# RF_drv_v2.net
KiCad netlist of a schematic drawn in Altium Designer
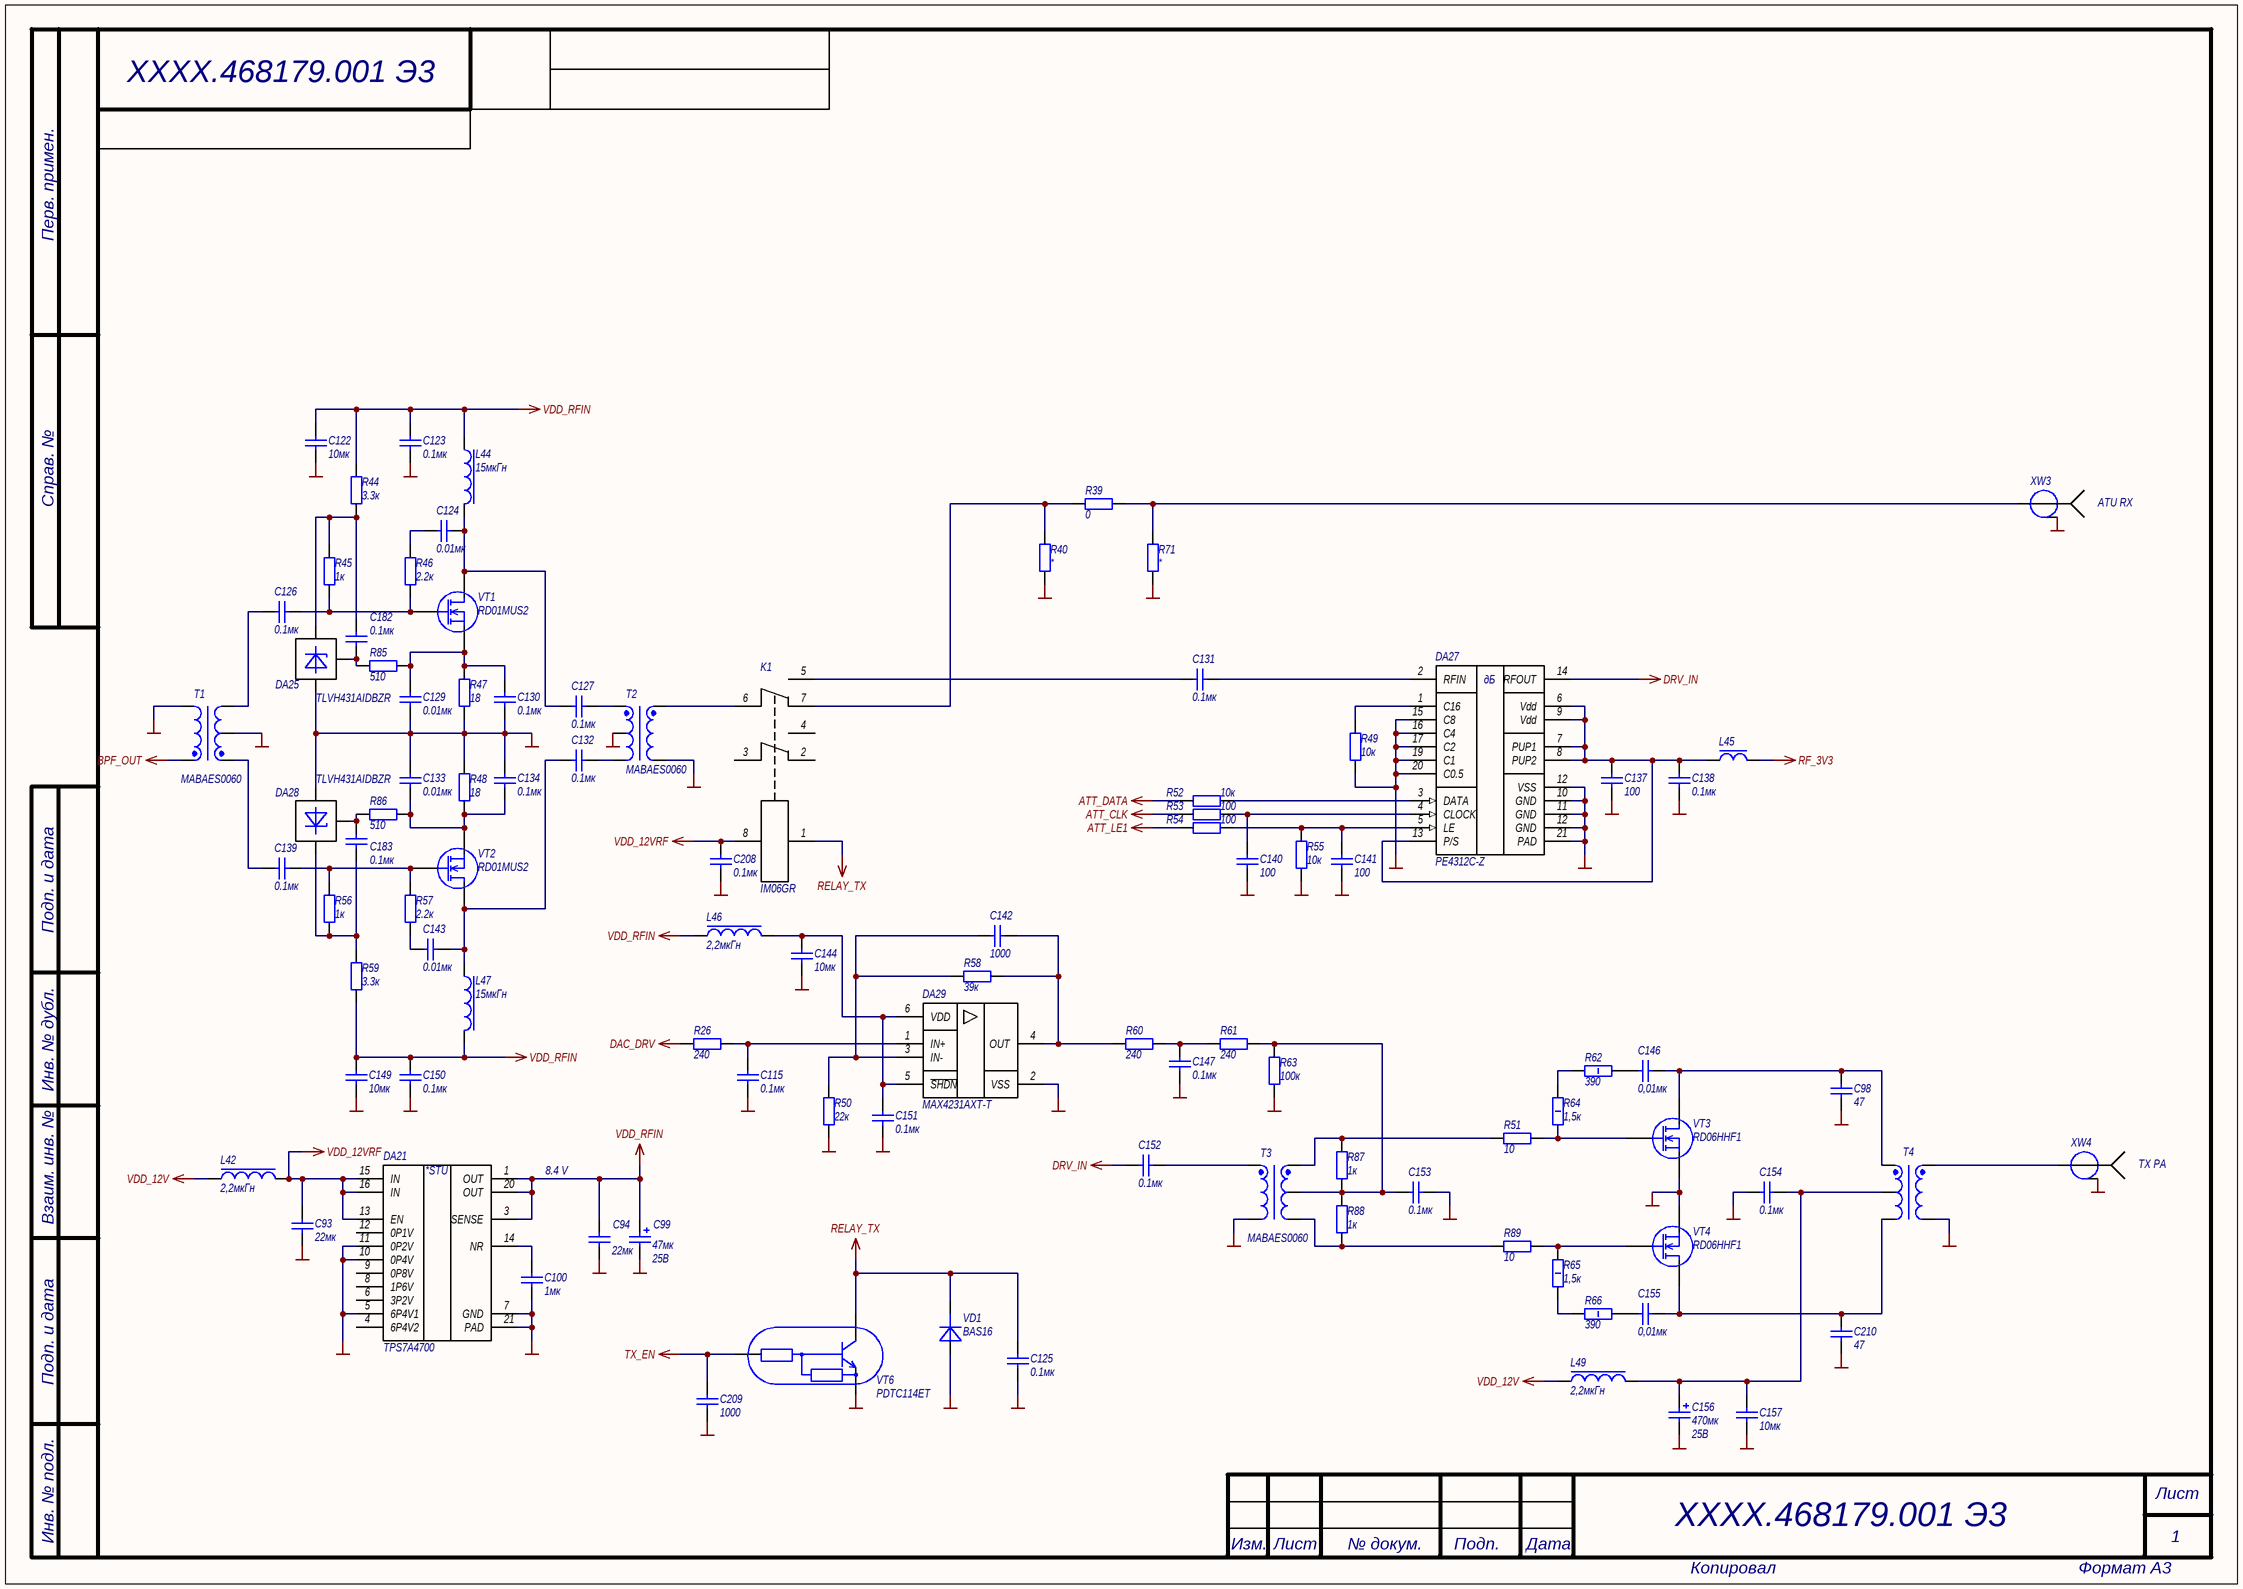
[diagram p0: RF_drv_v2.SchDoc]

(export (version "E")
  (design (tool "Eeschema 10.0.6"))
  (components
    (comp (ref "C93")
      (value "22мк")
      (footprint "CAPC2012X12L")
      (description "Кер. ЧИП-конденсатор")
      (fields (field (name "MANUFACTURER") "TDK") (field (name "TOLERANCE") "±10%"))
      (libsource (lib "nels_caps") (part "Кер.ЧИП конд. 0805 22мкФ X5R 10% 16В"))
    )
    (comp (ref "C94")
      (value "22мк")
      (footprint "CAPC2012X12L")
      (description "Кер. ЧИП-конденсатор")
      (fields (field (name "MANUFACTURER") "TDK") (field (name "TOLERANCE") "±10%"))
      (libsource (lib "nels_caps") (part "Кер.ЧИП конд. 0805 22мкФ X5R 10% 16В"))
    )
    (comp (ref "C98")
      (value "47")
      (footprint "CAPC3216X19L")
      (description "Кер. ЧИП-конденсатор")
      (fields (field (name "MANUFACTURER") "WALSIN") (field (name "TOLERANCE") "±5%"))
      (libsource (lib "nels_caps") (part "Кер.ЧИП конд. 1206 47пФ NP0 5% 2000В"))
    )
    (comp (ref "C99")
      (value "47мк")
      (footprint "CAPMP7343X28L")
      (description "Тант. ЧИП-конденсатор")
      (fields
        (field (name "TOLERANCE") "±10%")
        (field (name "POWER/VOLTAGE") "25В")
        (field (name "PUBLISHER") "Altium Limited")
      )
      (libsource (lib "nels_caps") (part "Конденсатор танталовый SMD D case 47мкФ ±10% 25B"))
    )
    (comp (ref "C100")
      (value "1мк")
      (footprint "CAPC1005X06N")
      (description "Кер. ЧИП-конденсатор")
      (fields (field (name "TOLERANCE") "±10%"))
      (libsource (lib "nels_caps") (part "Кер.ЧИП конд. 0402 1мкФ X5R 10%, 10В"))
    )
    (comp (ref "C115")
      (value "0.1мк")
      (footprint "CAPC1005X06N")
      (description "Кер. ЧИП-конденсатор")
      (fields (field (name "TOLERANCE") "±10%"))
      (libsource (lib "nels") (part "Кер.ЧИП конд. 0402 0.1мкФ X7R 10%, 16В"))
    )
    (comp (ref "C122")
      (value "10мк")
      (footprint "CAPC3225X27L")
      (description "Кер. ЧИП-конденсатор")
      (fields (field (name "MANUFACTURER") "Murata") (field (name "TOLERANCE") "±20%"))
      (libsource (lib "nels_caps") (part "Кер.ЧИП конд. 1210 10мкФ X5R 20% 50В"))
    )
    (comp (ref "C123")
      (value "0.1мк")
      (footprint "CAPC1005X06N")
      (description "Кер. ЧИП-конденсатор")
      (fields (field (name "TOLERANCE") "±10%"))
      (libsource (lib "nels") (part "Кер.ЧИП конд. 0402 0.1мкФ X7R 10%, 16В"))
    )
    (comp (ref "C124")
      (value "0.01мк")
      (footprint "CAPC1005X06N")
      (description "Кер. ЧИП-конденсатор")
      (fields (field (name "TOLERANCE") "±20%"))
      (libsource (lib "nels_caps") (part "Кер.ЧИП конд. 0402 0.01мкФ X7R 10%, 50В"))
    )
    (comp (ref "C125")
      (value "0.1мк")
      (footprint "CAPC1005X06N")
      (description "Кер. ЧИП-конденсатор")
      (fields (field (name "TOLERANCE") "±10%"))
      (libsource (lib "nels") (part "Кер.ЧИП конд. 0402 0.1мкФ X7R 10%, 16В"))
    )
    (comp (ref "C126")
      (value "0.1мк")
      (footprint "CAPC1005X06N")
      (description "Кер. ЧИП-конденсатор")
      (fields (field (name "TOLERANCE") "±10%"))
      (libsource (lib "nels") (part "Кер.ЧИП конд. 0402 0.1мкФ X7R 10%, 16В"))
    )
    (comp (ref "C127")
      (value "0.1мк")
      (footprint "CAPC1608X08L")
      (description "Кер. ЧИП-конденсатор")
      (fields (field (name "TOLERANCE") "±10%") (field (name "MANUFACTURER") "Murata"))
      (libsource (lib "nels_caps") (part "Кер.ЧИП конд. 0603 0.1мкФ X7R 10% 50В"))
    )
    (comp (ref "C129")
      (value "0.01мк")
      (footprint "CAPC1005X06N")
      (description "Кер. ЧИП-конденсатор")
      (fields (field (name "TOLERANCE") "±20%"))
      (libsource (lib "nels_caps") (part "Кер.ЧИП конд. 0402 0.01мкФ X7R 10%, 50В"))
    )
    (comp (ref "C130")
      (value "0.1мк")
      (footprint "CAPC1005X06N")
      (description "Кер. ЧИП-конденсатор")
      (fields (field (name "TOLERANCE") "±10%"))
      (libsource (lib "nels") (part "Кер.ЧИП конд. 0402 0.1мкФ X7R 10%, 16В"))
    )
    (comp (ref "C131")
      (value "0.1мк")
      (footprint "CAPC1608X08L")
      (description "Кер. ЧИП-конденсатор")
      (fields (field (name "TOLERANCE") "±10%") (field (name "MANUFACTURER") "Murata"))
      (libsource (lib "nels_caps") (part "Кер.ЧИП конд. 0603 0.1мкФ X7R 10% 50В"))
    )
    (comp (ref "C132")
      (value "0.1мк")
      (footprint "CAPC1608X08L")
      (description "Кер. ЧИП-конденсатор")
      (fields (field (name "TOLERANCE") "±10%") (field (name "MANUFACTURER") "Murata"))
      (libsource (lib "nels_caps") (part "Кер.ЧИП конд. 0603 0.1мкФ X7R 10% 50В"))
    )
    (comp (ref "C133")
      (value "0.01мк")
      (footprint "CAPC1005X06N")
      (description "Кер. ЧИП-конденсатор")
      (fields (field (name "TOLERANCE") "±20%"))
      (libsource (lib "nels_caps") (part "Кер.ЧИП конд. 0402 0.01мкФ X7R 10%, 50В"))
    )
    (comp (ref "C134")
      (value "0.1мк")
      (footprint "CAPC1005X06N")
      (description "Кер. ЧИП-конденсатор")
      (fields (field (name "TOLERANCE") "±10%"))
      (libsource (lib "nels") (part "Кер.ЧИП конд. 0402 0.1мкФ X7R 10%, 16В"))
    )
    (comp (ref "C137")
      (value "100")
      (footprint "CAPC1005X06N")
      (description "Кер. ЧИП-конденсатор")
      (fields (field (name "TOLERANCE") "±5%"))
      (libsource (lib "nels_caps") (part "Кер.ЧИП конд. 0402 100пФ NPO 5%, 50В"))
    )
    (comp (ref "C138")
      (value "0.1мк")
      (footprint "CAPC1005X06N")
      (description "Кер. ЧИП-конденсатор")
      (fields (field (name "TOLERANCE") "±10%"))
      (libsource (lib "nels") (part "Кер.ЧИП конд. 0402 0.1мкФ X7R 10%, 16В"))
    )
    (comp (ref "C139")
      (value "0.1мк")
      (footprint "CAPC1005X06N")
      (description "Кер. ЧИП-конденсатор")
      (fields (field (name "TOLERANCE") "±10%"))
      (libsource (lib "nels") (part "Кер.ЧИП конд. 0402 0.1мкФ X7R 10%, 16В"))
    )
    (comp (ref "C140")
      (value "100")
      (footprint "CAPC1005X06N")
      (description "Кер. ЧИП-конденсатор")
      (fields (field (name "TOLERANCE") "±5%"))
      (libsource (lib "nels_caps") (part "Кер.ЧИП конд. 0402 100пФ NPO 5%, 50В"))
    )
    (comp (ref "C141")
      (value "100")
      (footprint "CAPC1005X06N")
      (description "Кер. ЧИП-конденсатор")
      (fields (field (name "TOLERANCE") "±5%"))
      (libsource (lib "nels_caps") (part "Кер.ЧИП конд. 0402 100пФ NPO 5%, 50В"))
    )
    (comp (ref "C142")
      (value "1000")
      (footprint "CAPC1005X06N")
      (description "Кер. ЧИП-конденсатор")
      (fields (field (name "TOLERANCE") "±5%"))
      (libsource (lib "nels_caps") (part "Кер.ЧИП конд. 0402 1000пФ NP0 5%, 50В"))
    )
    (comp (ref "C143")
      (value "0.01мк")
      (footprint "CAPC1005X06N")
      (description "Кер. ЧИП-конденсатор")
      (fields (field (name "TOLERANCE") "±20%"))
      (libsource (lib "nels_caps") (part "Кер.ЧИП конд. 0402 0.01мкФ X7R 10%, 50В"))
    )
    (comp (ref "C144")
      (value "10мк")
      (footprint "CAPC3225X27L")
      (description "Кер. ЧИП-конденсатор")
      (fields (field (name "MANUFACTURER") "Murata") (field (name "TOLERANCE") "±20%"))
      (libsource (lib "nels_caps") (part "Кер.ЧИП конд. 1210 10мкФ X5R 20% 50В"))
    )
    (comp (ref "C146")
      (value "0,01мк")
      (footprint "CAPC2012X12L")
      (description "Кер. ЧИП-конденсатор")
      (fields (field (name "MANUFACTURER") "Murate") (field (name "TOLERANCE") "±10%"))
      (libsource (lib "nels_caps") (part "Кер.ЧИП конд. 0805 0,01 мкФ X7R 10% 250В"))
    )
    (comp (ref "C147")
      (value "0.1мк")
      (footprint "CAPC1005X06N")
      (description "Кер. ЧИП-конденсатор")
      (fields (field (name "TOLERANCE") "±10%"))
      (libsource (lib "nels") (part "Кер.ЧИП конд. 0402 0.1мкФ X7R 10%, 16В"))
    )
    (comp (ref "C149")
      (value "10мк")
      (footprint "CAPC3225X27L")
      (description "Кер. ЧИП-конденсатор")
      (fields (field (name "MANUFACTURER") "Murata") (field (name "TOLERANCE") "±20%"))
      (libsource (lib "nels_caps") (part "Кер.ЧИП конд. 1210 10мкФ X5R 20% 50В"))
    )
    (comp (ref "C150")
      (value "0.1мк")
      (footprint "CAPC1005X06N")
      (description "Кер. ЧИП-конденсатор")
      (fields (field (name "TOLERANCE") "±10%"))
      (libsource (lib "nels") (part "Кер.ЧИП конд. 0402 0.1мкФ X7R 10%, 16В"))
    )
    (comp (ref "C151")
      (value "0.1мк")
      (footprint "CAPC1005X06N")
      (description "Кер. ЧИП-конденсатор")
      (fields (field (name "TOLERANCE") "±10%"))
      (libsource (lib "nels") (part "Кер.ЧИП конд. 0402 0.1мкФ X7R 10%, 16В"))
    )
    (comp (ref "C152")
      (value "0.1мк")
      (footprint "CAPC1608X08L")
      (description "Кер. ЧИП-конденсатор")
      (fields (field (name "TOLERANCE") "±10%") (field (name "MANUFACTURER") "Murata"))
      (libsource (lib "nels_caps") (part "Кер.ЧИП конд. 0603 0.1мкФ X7R 10% 50В"))
    )
    (comp (ref "C153")
      (value "0.1мк")
      (footprint "CAPC1608X08L")
      (description "Кер. ЧИП-конденсатор")
      (fields (field (name "TOLERANCE") "±10%") (field (name "MANUFACTURER") "Murata"))
      (libsource (lib "nels_caps") (part "Кер.ЧИП конд. 0603 0.1мкФ X7R 10% 50В"))
    )
    (comp (ref "C154")
      (value "0.1мк")
      (footprint "CAPC1608X08L")
      (description "Кер. ЧИП-конденсатор")
      (fields (field (name "TOLERANCE") "±10%") (field (name "MANUFACTURER") "Murata"))
      (libsource (lib "nels_caps") (part "Кер.ЧИП конд. 0603 0.1мкФ X7R 10% 50В"))
    )
    (comp (ref "C155")
      (value "0,01мк")
      (footprint "CAPC2012X12L")
      (description "Кер. ЧИП-конденсатор")
      (fields (field (name "MANUFACTURER") "Murate") (field (name "TOLERANCE") "±10%"))
      (libsource (lib "nels_caps") (part "Кер.ЧИП конд. 0805 0,01 мкФ X7R 10% 250В"))
    )
    (comp (ref "C156")
      (value "470мк")
      (footprint "CAPAE116103X105N")
      (description "Гибридный ЧИП-конденсатор")
      (fields
        (field (name "TOLERANCE") "±20%")
        (field (name "MANUFACTURERPARTNUMBER") "EEHZK1E471P")
        (field (name "POWER/VOLTAGE") "25В")
        (field (name "PUBLISHER") "Altium Limited")
      )
      (libsource (lib "nels_caps") (part "Конденсатор гибридный SMD 470мкФ ±20% 25В"))
    )
    (comp (ref "C157")
      (value "10мк")
      (footprint "CAPC3225X27L")
      (description "Кер. ЧИП-конденсатор")
      (fields (field (name "MANUFACTURER") "Murata") (field (name "TOLERANCE") "±20%"))
      (libsource (lib "nels_caps") (part "Кер.ЧИП конд. 1210 10мкФ X5R 20% 50В"))
    )
    (comp (ref "C182")
      (value "0.1мк")
      (footprint "CAPC1005X06N")
      (description "Кер. ЧИП-конденсатор")
      (fields (field (name "TOLERANCE") "±10%"))
      (libsource (lib "nels") (part "Кер.ЧИП конд. 0402 0.1мкФ X7R 10%, 16В"))
    )
    (comp (ref "C183")
      (value "0.1мк")
      (footprint "CAPC1005X06N")
      (description "Кер. ЧИП-конденсатор")
      (fields (field (name "TOLERANCE") "±10%"))
      (libsource (lib "nels") (part "Кер.ЧИП конд. 0402 0.1мкФ X7R 10%, 16В"))
    )
    (comp (ref "C208")
      (value "0.1мк")
      (footprint "CAPC1005X06N")
      (description "Кер. ЧИП-конденсатор")
      (fields (field (name "TOLERANCE") "±10%"))
      (libsource (lib "nels") (part "Кер.ЧИП конд. 0402 0.1мкФ X7R 10%, 16В"))
    )
    (comp (ref "C209")
      (value "1000")
      (footprint "CAPC1005X06N")
      (description "Кер. ЧИП-конденсатор")
      (fields (field (name "TOLERANCE") "±5%"))
      (libsource (lib "nels_caps") (part "Кер.ЧИП конд. 0402 1000пФ NP0 5%, 50В"))
    )
    (comp (ref "C210")
      (value "47")
      (footprint "CAPC3216X19L")
      (description "Кер. ЧИП-конденсатор")
      (fields (field (name "MANUFACTURER") "WALSIN") (field (name "TOLERANCE") "±5%"))
      (libsource (lib "nels_caps") (part "Кер.ЧИП конд. 1206 47пФ NP0 5% 2000В"))
    )
    (comp (ref "DA21")
      (value "TPS7A4700")
      (footprint "QFN65P500X500X100_HS-21L")
      (description "36-V, 1-A, 4-µVRMS, RF LDO Voltage Regulator")
      (fields (field (name "MANUFACTURER") "TI"))
      (libsource (lib "nels_chip") (part "Микросхема TPS7A4700RGW"))
    )
    (comp (ref "DA25")
      (value "TLVH431AIDBZR")
      (footprint "SOT23_N")
      (description "Low-Voltage Adjustable Precision Shunt Regulator")
      (fields (field (name "MANUFACTURER") "TI"))
      (libsource (lib "nels_other") (part "ЧИП регулятор TLVH431AIDBZR"))
    )
    (comp (ref "DA27")
      (value "PE4312C-Z")
      (footprint "QFN50P400X400X80_HS-21L")
      (description "RF Digital Step Attenuator 6-bit, 31.5 dB, 1 MHz–4 GHz")
      (fields (field (name "MANUFACTURER") "Peregrine"))
      (libsource (lib "nels_chip") (part "Микросхема PE4312C-Z"))
    )
    (comp (ref "DA28")
      (value "TLVH431AIDBZR")
      (footprint "SOT23_N")
      (description "Low-Voltage Adjustable Precision Shunt Regulator")
      (fields (field (name "MANUFACTURER") "TI"))
      (libsource (lib "") (part "ЧИП регулятор TLVH431AIDBZR_1"))
    )
    (comp (ref "DA29")
      (value "MAX4231AXT-T")
      (footprint "TSOP65P210X100-6L")
      (description "High-Output-Drive, 10MHz, 10V/μs,  Rail-to-Rail I/O Op Amps with Shutdown in SC70")
      (fields (field (name "MANUFACTURER") "MAXIM"))
      (libsource (lib "nels_chip") (part "Микросхема MAX4231AXT-T"))
    )
    (comp (ref "K1")
      (value "IM06GR")
      (footprint "IM Relay GR")
      (description "Signal Relay 12VDC")
      (libsource (lib "nels_other") (part "Реле IM06GR"))
    )
    (comp (ref "L42")
      (value "2,2мкГн")
      (footprint "CSAB0420")
      (description "Molding Power Choke")
      (fields
        (field (name "MANUFACTURER") "Vishay")
        (field (name "MANUFACTURERPARTNUMBER") "IHLP1616ABER1R0M11")
      )
      (libsource (lib "nels_ind") (part "ЧИП индуктивность CSAB0420-2R2M"))
    )
    (comp (ref "L44")
      (value "15мкГн")
      (footprint "Coilcraft-1812FS")
      (description "High SRF, High Current Inductors")
      (fields
        (field (name "MANUFACTURER") "Сoilcraft")
        (field (name "MANUFACTURERPARTNUMBER") "1812PS-683KLC")
      )
      (libsource (lib "nels_ind") (part "ЧИП индуктивность 1812FS-153"))
    )
    (comp (ref "L45")
      (value "BLM18PG121SN1D")
      (footprint "INDC1608X08L")
      (description "SMD EMI Suppression Filter EMIFIL")
      (fields (field (name "MANUFACTURER") "Murata"))
      (libsource (lib "nels_ind") (part "ЧИП дроссель 0603 BLM18PG121SN1D"))
    )
    (comp (ref "L46")
      (value "2,2мкГн")
      (footprint "CSAB0420")
      (description "Molding Power Choke")
      (fields
        (field (name "MANUFACTURER") "Vishay")
        (field (name "MANUFACTURERPARTNUMBER") "IHLP1616ABER1R0M11")
      )
      (libsource (lib "nels_ind") (part "ЧИП индуктивность CSAB0420-2R2M"))
    )
    (comp (ref "L47")
      (value "15мкГн")
      (footprint "Coilcraft-1812FS")
      (description "High SRF, High Current Inductors")
      (fields
        (field (name "MANUFACTURER") "Сoilcraft")
        (field (name "MANUFACTURERPARTNUMBER") "1812PS-683KLC")
      )
      (libsource (lib "nels_ind") (part "ЧИП индуктивность 1812FS-153"))
    )
    (comp (ref "L49")
      (value "2,2мкГн")
      (footprint "CSAB0420")
      (description "Molding Power Choke")
      (fields
        (field (name "MANUFACTURER") "Vishay")
        (field (name "MANUFACTURERPARTNUMBER") "IHLP1616ABER1R0M11")
      )
      (libsource (lib "nels_ind") (part "ЧИП индуктивность CSAB0420-2R2M"))
    )
    (comp (ref "R26")
      (value "240")
      (footprint "RESC1005X06N")
      (description "ЧИП-резистор")
      (fields (field (name "TOLERANCE") "±5%"))
      (libsource (lib "nels_res") (part "Чип резистор 0402 240 Ом, 5%"))
    )
    (comp (ref "R39")
      (value "0")
      (footprint "RESC1005X06N")
      (description "ЧИП-резистор")
      (fields (field (name "TOLERANCE") "±5%"))
      (libsource (lib "nels_res") (part "Чип резистор 0402 0 Ом"))
    )
    (comp (ref "R40")
      (value "*")
      (footprint "RESC1005X06N")
      (description "ЧИП-резистор")
      (fields (field (name "TOLERANCE") "±5%") (field (name "ALTIUM_VALUE") "*"))
      (libsource (lib "nels_res") (part "Чип резистор 0402 *"))
    )
    (comp (ref "R44")
      (value "3.3к")
      (footprint "RESC1005X06N")
      (description "ЧИП-резистор")
      (fields (field (name "TOLERANCE") "±5%"))
      (libsource (lib "nels_res") (part "Чип резистор 0402 3,3 кОм, 5%"))
    )
    (comp (ref "R45")
      (value "1к")
      (footprint "RESC1005X06N")
      (description "ЧИП-резистор")
      (fields (field (name "TOLERANCE") "±5%"))
      (libsource (lib "nels_res") (part "Чип резистор 0402 1 кОм, 5%"))
    )
    (comp (ref "R46")
      (value "2.2к")
      (footprint "RESC1005X06N")
      (description "ЧИП-резистор")
      (fields (field (name "TOLERANCE") "±5%"))
      (libsource (lib "nels_res") (part "Чип резистор 0402 2,2 кОм, 5%"))
    )
    (comp (ref "R47")
      (value "18")
      (footprint "RESC2012X05L")
      (description "ЧИП-резистор")
      (fields (field (name "TOLERANCE") "±5%"))
      (libsource (lib "nels_res") (part "Чип резистор 0805 18 Ом, 5%"))
    )
    (comp (ref "R48")
      (value "18")
      (footprint "RESC2012X05L")
      (description "ЧИП-резистор")
      (fields (field (name "TOLERANCE") "±5%"))
      (libsource (lib "nels_res") (part "Чип резистор 0805 18 Ом, 5%"))
    )
    (comp (ref "R49")
      (value "10к")
      (footprint "RESC1005X06N")
      (description "ЧИП-резистор")
      (fields (field (name "TOLERANCE") "±5%"))
      (libsource (lib "") (part "Чип резистор 0402 10 кОм, 5%_2"))
    )
    (comp (ref "R50")
      (value "22к")
      (footprint "RESC1005X06N")
      (description "ЧИП-резистор")
      (fields (field (name "TOLERANCE") "±5%"))
      (libsource (lib "nels_res") (part "Чип резистор 0402 22 кОм, 5%"))
    )
    (comp (ref "R51")
      (value "10")
      (footprint "RESC1005X06N")
      (description "ЧИП-резистор")
      (fields (field (name "TOLERANCE") "±5%"))
      (libsource (lib "nels_res") (part "Чип резистор 0402 10 Ом, 5%"))
    )
    (comp (ref "R52")
      (value "10к")
      (footprint "RESC1005X06N")
      (description "ЧИП-резистор")
      (fields (field (name "TOLERANCE") "±5%"))
      (libsource (lib "nels_res") (part "Чип резистор 0402 10 кОм, 5%"))
    )
    (comp (ref "R53")
      (value "100")
      (footprint "RESC1005X06N")
      (description "ЧИП-резистор")
      (fields (field (name "TOLERANCE") "±5%"))
      (libsource (lib "nels_res") (part "Чип резистор 0402 100 Ом, 5%"))
    )
    (comp (ref "R54")
      (value "100")
      (footprint "RESC1005X06N")
      (description "ЧИП-резистор")
      (fields (field (name "TOLERANCE") "±5%"))
      (libsource (lib "nels_res") (part "Чип резистор 0402 100 Ом, 5%"))
    )
    (comp (ref "R55")
      (value "10к")
      (footprint "RESC1005X06N")
      (description "ЧИП-резистор")
      (fields (field (name "TOLERANCE") "±5%"))
      (libsource (lib "") (part "Чип резистор 0402 10 кОм, 5%_1"))
    )
    (comp (ref "R56")
      (value "1к")
      (footprint "RESC1005X06N")
      (description "ЧИП-резистор")
      (fields (field (name "TOLERANCE") "±5%"))
      (libsource (lib "nels_res") (part "Чип резистор 0402 1 кОм, 5%"))
    )
    (comp (ref "R57")
      (value "2.2к")
      (footprint "RESC1005X06N")
      (description "ЧИП-резистор")
      (fields (field (name "TOLERANCE") "±5%"))
      (libsource (lib "nels_res") (part "Чип резистор 0402 2,2 кОм, 5%"))
    )
    (comp (ref "R58")
      (value "39к")
      (footprint "RESC1005X06N")
      (description "ЧИП-резистор")
      (fields (field (name "TOLERANCE") "±5%"))
      (libsource (lib "nels_res") (part "Чип резистор 0402 39 кОм, 5%"))
    )
    (comp (ref "R59")
      (value "3.3к")
      (footprint "RESC1005X06N")
      (description "ЧИП-резистор")
      (fields (field (name "TOLERANCE") "±5%"))
      (libsource (lib "nels_res") (part "Чип резистор 0402 3,3 кОм, 5%"))
    )
    (comp (ref "R60")
      (value "240")
      (footprint "RESC1005X06N")
      (description "ЧИП-резистор")
      (fields (field (name "TOLERANCE") "±5%"))
      (libsource (lib "nels_res") (part "Чип резистор 0402 240 Ом, 5%"))
    )
    (comp (ref "R61")
      (value "240")
      (footprint "RESC1005X06N")
      (description "ЧИП-резистор")
      (fields (field (name "TOLERANCE") "±5%"))
      (libsource (lib "nels_res") (part "Чип резистор 0402 240 Ом, 5%"))
    )
    (comp (ref "R62")
      (value "390")
      (footprint "RESC3216X04L")
      (description "ЧИП-резистор")
      (fields (field (name "TOLERANCE") "±5%") (field (name "MANUFACTURER") "ROHM"))
      (libsource (lib "nels_res") (part "Чип резистор 1206 390 Ом, 5%"))
    )
    (comp (ref "R63")
      (value "100к")
      (footprint "RESC1005X06N")
      (description "ЧИП-резистор")
      (fields (field (name "TOLERANCE") "±5%"))
      (libsource (lib "nels_res") (part "Чип резистор 0402 100 кОм, 5%"))
    )
    (comp (ref "R64")
      (value "1,5к")
      (footprint "RESC3216X04L")
      (description "ЧИП-резистор")
      (fields (field (name "TOLERANCE") "±5%") (field (name "MANUFACTURER") "ROHM"))
      (libsource (lib "nels_res") (part "Чип резистор 1206 1,5 кОм, 5%"))
    )
    (comp (ref "R65")
      (value "1,5к")
      (footprint "RESC3216X04L")
      (description "ЧИП-резистор")
      (fields (field (name "TOLERANCE") "±5%") (field (name "MANUFACTURER") "ROHM"))
      (libsource (lib "nels_res") (part "Чип резистор 1206 1,5 кОм, 5%"))
    )
    (comp (ref "R66")
      (value "390")
      (footprint "RESC3216X04L")
      (description "ЧИП-резистор")
      (fields (field (name "TOLERANCE") "±5%") (field (name "MANUFACTURER") "ROHM"))
      (libsource (lib "nels_res") (part "Чип резистор 1206 390 Ом, 5%"))
    )
    (comp (ref "R71")
      (value "*")
      (footprint "RESC1005X06N")
      (description "ЧИП-резистор")
      (fields (field (name "TOLERANCE") "±5%") (field (name "ALTIUM_VALUE") "*"))
      (libsource (lib "nels_res") (part "Чип резистор 0402 *"))
    )
    (comp (ref "R85")
      (value "510")
      (footprint "RESC1005X06N")
      (description "ЧИП-резистор")
      (fields (field (name "TOLERANCE") "±5%"))
      (libsource (lib "nels_res") (part "Чип резистор 0402 510 Ом, 5%"))
    )
    (comp (ref "R86")
      (value "510")
      (footprint "RESC1005X06N")
      (description "ЧИП-резистор")
      (fields (field (name "TOLERANCE") "±5%"))
      (libsource (lib "nels_res") (part "Чип резистор 0402 510 Ом, 5%"))
    )
    (comp (ref "R87")
      (value "1к")
      (footprint "RESC1005X06N")
      (description "ЧИП-резистор")
      (fields (field (name "TOLERANCE") "±5%"))
      (libsource (lib "nels_res") (part "Чип резистор 0402 1 кОм, 5%"))
    )
    (comp (ref "R88")
      (value "1к")
      (footprint "RESC1005X06N")
      (description "ЧИП-резистор")
      (fields (field (name "TOLERANCE") "±5%"))
      (libsource (lib "nels_res") (part "Чип резистор 0402 1 кОм, 5%"))
    )
    (comp (ref "R89")
      (value "10")
      (footprint "RESC1005X06N")
      (description "ЧИП-резистор")
      (fields (field (name "TOLERANCE") "±5%"))
      (libsource (lib "nels_res") (part "Чип резистор 0402 10 Ом, 5%"))
    )
    (comp (ref "T1")
      (value "MABAES0060")
      (footprint "SM-22 package")
      (description "RF 1:1 Flux Coupled Transformer 0.3 - 200 MHz")
      (fields (field (name "MANUFACTURER") "MACOM"))
      (libsource (lib "nels_ind") (part "ЧИП трансформатор MABAES0060"))
    )
    (comp (ref "T2")
      (value "MABAES0060")
      (footprint "SM-22 package")
      (description "RF 1:1 Flux Coupled Transformer 0.3 - 200 MHz")
      (fields (field (name "MANUFACTURER") "MACOM"))
      (libsource (lib "nels_ind") (part "ЧИП трансформатор MABAES0060"))
    )
    (comp (ref "T3")
      (value "MABAES0060")
      (footprint "SM-22 package")
      (description "RF 1:1 Flux Coupled Transformer 0.3 - 200 MHz")
      (fields (field (name "MANUFACTURER") "MACOM"))
      (libsource (lib "") (part "ЧИП трансформатор MABAES0060_1"))
    )
    (comp (ref "T4")
      (value "Трансформатор PUM_OUT")
      (footprint "Transformer_KV_PA20_0UT_2xBN-43-302_V1")
      (fields
        (field (name "MANUFACTURER") "НЕЛС")
        (field (name "MANUFACTURER PART NUMBER") "Трансформатор PUM_OUT АНЕЛ.671143.003")
      )
      (libsource (lib "nels_ind") (part "Transformer_KV_PA20_OUT"))
    )
    (comp (ref "VD1")
      (value "BAS16")
      (footprint "SOT23_N")
      (description "High-speed switching diodes")
      (fields (field (name "MANUFACTURER") "Nexperia"))
      (libsource (lib "nels_other") (part "ЧИП диод BAS16"))
    )
    (comp (ref "VT1")
      (value "RD01MUS2")
      (footprint "SOT89-150P330X160-3N")
      (description "Silicon MOSFET Power Transistor 520MHz, 1W, 7.2V")
      (libsource (lib "nels_other") (part "ЧИП транзистор RD01MUS2"))
    )
    (comp (ref "VT2")
      (value "RD01MUS2")
      (footprint "SOT89-150P330X160-3N")
      (description "Silicon MOSFET Power Transistor 520MHz, 1W, 7.2V")
      (libsource (lib "nels_other") (part "ЧИП транзистор RD01MUS2"))
    )
    (comp (ref "VT3")
      (value "RD06HHF1")
      (footprint "TO-220HS")
      (description "Silicon MOSFET Power Transistor 30MHz,6W")
      (libsource (lib "nels_other") (part "ЧИП транзистор RD06HHF1"))
    )
    (comp (ref "VT4")
      (value "RD06HHF1")
      (footprint "TO-220HS")
      (description "Silicon MOSFET Power Transistor 30MHz,6W")
      (libsource (lib "nels_other") (part "ЧИП транзистор RD06HHF1"))
    )
    (comp (ref "VT6")
      (value "PDTC114ET")
      (footprint "SOT23_N")
      (description "NPN resistor-equipped transistors;  R1 = 10 k, R2 = 10")
      (libsource (lib "nels_other") (part "ЧИП транзистор PDTC114ET"))
    )
    (comp (ref "XW3")
      (value "SMA-JR")
      (footprint "SMA-JR")
      (description "SMA-JR Разъем SMA гнездо на плату, прямой угол")
      (libsource (lib "nels_conn") (part "Соединитель коаксиальный SMA-JR"))
    )
    (comp (ref "XW4")
      (value "SMA-JR")
      (footprint "SMA-JR")
      (description "SMA-JR Разъем SMA гнездо на плату, прямой угол")
      (libsource (lib "nels_conn") (part "Соединитель коаксиальный SMA-JR"))
    )
  )
  (nets
    (net (code "1") (name "ATT_CLK") (class "Default")
      (node (ref "R53") (pin "2") (pinfunction "2_2") (pintype "passive"))
    )
    (net (code "2") (name "ATT_DATA") (class "Default")
      (node (ref "R52") (pin "2") (pinfunction "2_2") (pintype "passive"))
    )
    (net (code "3") (name "ATT_LE1") (class "Default")
      (node (ref "R54") (pin "2") (pinfunction "2_2") (pintype "passive"))
    )
    (net (code "4") (name "BPF_OUT") (class "Default")
      (node (ref "T1") (pin "5") (pinfunction "PRIMARY_DOT_5") (pintype "passive"))
    )
    (net (code "5") (name "DAC_DRV") (class "Default")
      (node (ref "R26") (pin "1") (pinfunction "1_1") (pintype "passive"))
    )
    (net (code "6") (name "DRV_IN") (class "Default")
      (node (ref "C152") (pin "2") (pinfunction "2_2") (pintype "passive"))
      (node (ref "DA27") (pin "14") (pinfunction "RFOUT_14") (pintype "passive"))
    )
    (net (code "7") (name "GND") (class "Default")
      (node (ref "C100") (pin "1") (pinfunction "1_1") (pintype "passive"))
      (node (ref "C115") (pin "2") (pinfunction "2_2") (pintype "passive"))
      (node (ref "C122") (pin "1") (pinfunction "1_1") (pintype "passive"))
      (node (ref "C123") (pin "2") (pinfunction "2_2") (pintype "passive"))
      (node (ref "C125") (pin "2") (pinfunction "2_2") (pintype "passive"))
      (node (ref "C129") (pin "2") (pinfunction "2_2") (pintype "passive"))
      (node (ref "C130") (pin "2") (pinfunction "2_2") (pintype "passive"))
      (node (ref "C133") (pin "1") (pinfunction "1_1") (pintype "passive"))
      (node (ref "C134") (pin "1") (pinfunction "1_1") (pintype "passive"))
      (node (ref "C137") (pin "1") (pinfunction "1_1") (pintype "passive"))
      (node (ref "C138") (pin "1") (pinfunction "1_1") (pintype "passive"))
      (node (ref "C140") (pin "1") (pinfunction "1_1") (pintype "passive"))
      (node (ref "C141") (pin "1") (pinfunction "1_1") (pintype "passive"))
      (node (ref "C144") (pin "1") (pinfunction "1_1") (pintype "passive"))
      (node (ref "C147") (pin "2") (pinfunction "2_2") (pintype "passive"))
      (node (ref "C149") (pin "1") (pinfunction "1_1") (pintype "passive"))
      (node (ref "C150") (pin "2") (pinfunction "2_2") (pintype "passive"))
      (node (ref "C151") (pin "2") (pinfunction "2_2") (pintype "passive"))
      (node (ref "C153") (pin "1") (pinfunction "1_1") (pintype "passive"))
      (node (ref "C154") (pin "1") (pinfunction "1_1") (pintype "passive"))
      (node (ref "C156") (pin "2") (pinfunction "2_2") (pintype "passive"))
      (node (ref "C157") (pin "1") (pinfunction "1_1") (pintype "passive"))
      (node (ref "C208") (pin "2") (pinfunction "2_2") (pintype "passive"))
      (node (ref "C209") (pin "2") (pinfunction "2_2") (pintype "passive"))
      (node (ref "C210") (pin "2") (pinfunction "2_2") (pintype "passive"))
      (node (ref "C93") (pin "1") (pinfunction "1_1") (pintype "passive"))
      (node (ref "C94") (pin "1") (pinfunction "1_1") (pintype "passive"))
      (node (ref "C98") (pin "2") (pinfunction "2_2") (pintype "passive"))
      (node (ref "C99") (pin "2") (pinfunction "2_2") (pintype "passive"))
      (node (ref "DA21") (pin "10") (pinfunction "0P4V_10") (pintype "passive"))
      (node (ref "DA21") (pin "11") (pinfunction "0P2V_11") (pintype "passive"))
      (node (ref "DA21") (pin "21") (pinfunction "PAD_21") (pintype "passive"))
      (node (ref "DA21") (pin "5") (pinfunction "6P4V1_5") (pintype "passive"))
      (node (ref "DA21") (pin "7") (pinfunction "GND_7") (pintype "passive"))
      (node (ref "DA25") (pin "3") (pinfunction "A_3") (pintype "passive"))
      (node (ref "DA27") (pin "10") (pinfunction "GND_10") (pintype "power_in"))
      (node (ref "DA27") (pin "11") (pinfunction "GND_11") (pintype "power_in"))
      (node (ref "DA27") (pin "12") (pinfunction "GND_12") (pintype "power_in"))
      (node (ref "DA27") (pin "15") (pinfunction "C8_15") (pintype "passive"))
      (node (ref "DA27") (pin "16") (pinfunction "C4_16") (pintype "passive"))
      (node (ref "DA27") (pin "17") (pinfunction "C2_17") (pintype "passive"))
      (node (ref "DA27") (pin "19") (pinfunction "C1_19") (pintype "passive"))
      (node (ref "DA27") (pin "20") (pinfunction "C0.5_20") (pintype "passive"))
      (node (ref "DA27") (pin "21") (pinfunction "PAD_21") (pintype "power_in"))
      (node (ref "DA28") (pin "3") (pinfunction "A_3") (pintype "passive"))
      (node (ref "DA29") (pin "2") (pinfunction "VSS_2") (pintype "passive"))
      (node (ref "R40") (pin "2") (pinfunction "2_2") (pintype "passive"))
      (node (ref "R47") (pin "2") (pinfunction "2_2") (pintype "passive"))
      (node (ref "R48") (pin "1") (pinfunction "1_1") (pintype "passive"))
      (node (ref "R49") (pin "1") (pinfunction "1_1") (pintype "passive"))
      (node (ref "R50") (pin "1") (pinfunction "1_1") (pintype "passive"))
      (node (ref "R55") (pin "2") (pinfunction "2_2") (pintype "passive"))
      (node (ref "R63") (pin "2") (pinfunction "2_2") (pintype "passive"))
      (node (ref "R71") (pin "2") (pinfunction "2_2") (pintype "passive"))
      (node (ref "T1") (pin "2") (pinfunction "SECONARY_CT_2") (pintype "passive"))
      (node (ref "T1") (pin "4") (pinfunction "PRIMARY_4") (pintype "passive"))
      (node (ref "T2") (pin "2") (pinfunction "SECONARY_CT_2") (pintype "passive"))
      (node (ref "T2") (pin "4") (pinfunction "PRIMARY_4") (pintype "passive"))
      (node (ref "T3") (pin "4") (pinfunction "PRIMARY_4") (pintype "passive"))
      (node (ref "T4") (pin "5") (pinfunction "SECONDARY_5") (pintype "passive"))
      (node (ref "VD1") (pin "1") (pinfunction "A_1") (pintype "passive"))
      (node (ref "VT3") (pin "2") (pinfunction "S_2") (pintype "passive"))
      (node (ref "VT4") (pin "2") (pinfunction "S_2") (pintype "passive"))
      (node (ref "VT6") (pin "2") (pinfunction "E_2") (pintype "passive"))
      (node (ref "XW3") (pin "2") (pinfunction "2_2") (pintype "passive"))
      (node (ref "XW4") (pin "2") (pinfunction "2_2") (pintype "passive"))
    )
    (net (code "8") (name "Net-(C124-Pad1)") (class "Default")
      (node (ref "C124") (pin "1") (pinfunction "1_1") (pintype "passive"))
      (node (ref "R46") (pin "1") (pinfunction "1_1") (pintype "passive"))
    )
    (net (code "9") (name "Net-(C131-Pad2)") (class "Default")
      (node (ref "C131") (pin "2") (pinfunction "2_2") (pintype "passive"))
      (node (ref "K1") (pin "5") (pintype "passive"))
    )
    (net (code "10") (name "Net-(C143-Pad1)") (class "Default")
      (node (ref "C143") (pin "1") (pinfunction "1_1") (pintype "passive"))
      (node (ref "R57") (pin "2") (pinfunction "2_2") (pintype "passive"))
    )
    (net (code "11") (name "Net-(C146-Pad2)") (class "Default")
      (node (ref "C146") (pin "2") (pinfunction "2_2") (pintype "passive"))
      (node (ref "R62") (pin "2") (pinfunction "2_2") (pintype "passive"))
    )
    (net (code "12") (name "Net-(C147-Pad1)") (class "Default")
      (node (ref "C147") (pin "1") (pinfunction "1_1") (pintype "passive"))
      (node (ref "R60") (pin "2") (pinfunction "2_2") (pintype "passive"))
      (node (ref "R61") (pin "1") (pinfunction "1_1") (pintype "passive"))
    )
    (net (code "13") (name "Net-(C155-Pad2)") (class "Default")
      (node (ref "C155") (pin "2") (pinfunction "2_2") (pintype "passive"))
      (node (ref "R66") (pin "2") (pinfunction "2_2") (pintype "passive"))
    )
    (net (code "14") (name "Net-(DA21-NR)") (class "Default")
      (node (ref "C100") (pin "2") (pinfunction "2_2") (pintype "passive"))
      (node (ref "DA21") (pin "14") (pinfunction "NR_14") (pintype "passive"))
    )
    (net (code "15") (name "Net-(DA25-K)") (class "Default")
      (node (ref "C182") (pin "1") (pinfunction "1_1") (pintype "passive"))
      (node (ref "DA25") (pin "2") (pinfunction "K_2") (pintype "passive"))
      (node (ref "R44") (pin "1") (pinfunction "1_1") (pintype "passive"))
      (node (ref "R45") (pin "1") (pinfunction "1_1") (pintype "passive"))
    )
    (net (code "16") (name "Net-(DA25-REF)") (class "Default")
      (node (ref "C182") (pin "2") (pinfunction "2_2") (pintype "passive"))
      (node (ref "DA25") (pin "1") (pinfunction "REF_1") (pintype "passive"))
      (node (ref "R85") (pin "1") (pinfunction "1_1") (pintype "passive"))
    )
    (net (code "17") (name "Net-(DA27-C16)") (class "Default")
      (node (ref "DA27") (pin "1") (pinfunction "C16_1") (pintype "passive"))
      (node (ref "R49") (pin "2") (pinfunction "2_2") (pintype "passive"))
    )
    (net (code "18") (name "Net-(DA27-CLOCK)") (class "Default")
      (node (ref "C140") (pin "2") (pinfunction "2_2") (pintype "passive"))
      (node (ref "DA27") (pin "4") (pinfunction "CLOCK_4") (pintype "input"))
      (node (ref "R53") (pin "1") (pinfunction "1_1") (pintype "passive"))
    )
    (net (code "19") (name "Net-(DA27-DATA)") (class "Default")
      (node (ref "DA27") (pin "3") (pinfunction "DATA_3") (pintype "input"))
      (node (ref "R52") (pin "1") (pinfunction "1_1") (pintype "passive"))
    )
    (net (code "20") (name "Net-(DA27-LE)") (class "Default")
      (node (ref "C141") (pin "2") (pinfunction "2_2") (pintype "passive"))
      (node (ref "DA27") (pin "5") (pinfunction "LE_5") (pintype "input"))
      (node (ref "R54") (pin "1") (pinfunction "1_1") (pintype "passive"))
      (node (ref "R55") (pin "1") (pinfunction "1_1") (pintype "passive"))
    )
    (net (code "21") (name "Net-(DA27-PUP1)") (class "Default")
      (node (ref "C137") (pin "2") (pinfunction "2_2") (pintype "passive"))
      (node (ref "C138") (pin "2") (pinfunction "2_2") (pintype "passive"))
      (node (ref "DA27") (pin "13") (pinfunction "P/S_13") (pintype "passive"))
      (node (ref "DA27") (pin "6") (pinfunction "Vdd_6") (pintype "power_in"))
      (node (ref "DA27") (pin "7") (pinfunction "PUP1_7") (pintype "passive"))
      (node (ref "DA27") (pin "8") (pinfunction "PUP2_8") (pintype "passive"))
      (node (ref "DA27") (pin "9") (pinfunction "Vdd_9") (pintype "power_in"))
      (node (ref "L45") (pin "1") (pinfunction "1_1") (pintype "passive"))
    )
    (net (code "22") (name "Net-(DA27-RFIN)") (class "Default")
      (node (ref "C131") (pin "1") (pinfunction "1_1") (pintype "passive"))
      (node (ref "DA27") (pin "2") (pinfunction "RFIN_2") (pintype "passive"))
    )
    (net (code "23") (name "Net-(DA28-K)") (class "Default")
      (node (ref "C183") (pin "2") (pinfunction "2_2") (pintype "passive"))
      (node (ref "DA28") (pin "2") (pinfunction "K_2") (pintype "passive"))
      (node (ref "R56") (pin "2") (pinfunction "2_2") (pintype "passive"))
      (node (ref "R59") (pin "2") (pinfunction "2_2") (pintype "passive"))
    )
    (net (code "24") (name "Net-(DA28-REF)") (class "Default")
      (node (ref "C183") (pin "1") (pinfunction "1_1") (pintype "passive"))
      (node (ref "DA28") (pin "1") (pinfunction "REF_1") (pintype "passive"))
      (node (ref "R86") (pin "1") (pinfunction "1_1") (pintype "passive"))
    )
    (net (code "25") (name "Net-(DA29-IN+)") (class "Default")
      (node (ref "C115") (pin "1") (pinfunction "1_1") (pintype "passive"))
      (node (ref "DA29") (pin "1") (pinfunction "IN+_1") (pintype "passive"))
      (node (ref "R26") (pin "2") (pinfunction "2_2") (pintype "passive"))
    )
    (net (code "26") (name "Net-(DA29-IN-)") (class "Default")
      (node (ref "C142") (pin "1") (pinfunction "1_1") (pintype "passive"))
      (node (ref "DA29") (pin "3") (pinfunction "IN-_3") (pintype "passive"))
      (node (ref "R50") (pin "2") (pinfunction "2_2") (pintype "passive"))
      (node (ref "R58") (pin "1") (pinfunction "1_1") (pintype "passive"))
    )
    (net (code "27") (name "Net-(DA29-OUT)") (class "Default")
      (node (ref "C142") (pin "2") (pinfunction "2_2") (pintype "passive"))
      (node (ref "DA29") (pin "4") (pinfunction "OUT_4") (pintype "passive"))
      (node (ref "R58") (pin "2") (pinfunction "2_2") (pintype "passive"))
      (node (ref "R60") (pin "1") (pinfunction "1_1") (pintype "passive"))
    )
    (net (code "28") (name "Net-(DA29-VDD)") (class "Default")
      (node (ref "C144") (pin "2") (pinfunction "2_2") (pintype "passive"))
      (node (ref "C151") (pin "1") (pinfunction "1_1") (pintype "passive"))
      (node (ref "DA29") (pin "5") (pinfunction "~{SHDN}_5") (pintype "passive"))
      (node (ref "DA29") (pin "6") (pinfunction "VDD_6") (pintype "passive"))
      (node (ref "L46") (pin "2") (pinfunction "2_2") (pintype "passive"))
    )
    (net (code "29") (name "Net-(K1-Pad7)") (class "Default")
      (node (ref "K1") (pin "7") (pintype "passive"))
      (node (ref "R39") (pin "1") (pinfunction "1_1") (pintype "passive"))
      (node (ref "R40") (pin "1") (pinfunction "1_1") (pintype "passive"))
    )
    (net (code "30") (name "Net-(R39-Pad2)") (class "Default")
      (node (ref "R39") (pin "2") (pinfunction "2_2") (pintype "passive"))
      (node (ref "R71") (pin "1") (pinfunction "1_1") (pintype "passive"))
      (node (ref "XW3") (pin "1") (pinfunction "1_1") (pintype "passive"))
    )
    (net (code "31") (name "Net-(R62-Pad1)") (class "Default")
      (node (ref "R62") (pin "1") (pinfunction "1_1") (pintype "passive"))
      (node (ref "R64") (pin "2") (pinfunction "2_2") (pintype "passive"))
    )
    (net (code "32") (name "Net-(R65-Pad1)") (class "Default")
      (node (ref "R65") (pin "1") (pinfunction "1_1") (pintype "passive"))
      (node (ref "R66") (pin "1") (pinfunction "1_1") (pintype "passive"))
    )
    (net (code "33") (name "Net-(T1-SECONDARY)") (class "Default")
      (node (ref "C126") (pin "2") (pinfunction "2_2") (pintype "passive"))
      (node (ref "T1") (pin "3") (pinfunction "SECONDARY_3") (pintype "passive"))
    )
    (net (code "34") (name "Net-(T1-SECONDARY_DOT)") (class "Default")
      (node (ref "C139") (pin "2") (pinfunction "2_2") (pintype "passive"))
      (node (ref "T1") (pin "1") (pinfunction "SECONDARY_DOT_1") (pintype "passive"))
    )
    (net (code "35") (name "Net-(T2-PRIMARY_DOT)") (class "Default")
      (node (ref "K1") (pin "6") (pintype "passive"))
      (node (ref "T2") (pin "5") (pinfunction "PRIMARY_DOT_5") (pintype "passive"))
    )
    (net (code "36") (name "Net-(T2-SECONDARY)") (class "Default")
      (node (ref "C132") (pin "1") (pinfunction "1_1") (pintype "passive"))
      (node (ref "T2") (pin "3") (pinfunction "SECONDARY_3") (pintype "passive"))
    )
    (net (code "37") (name "Net-(T2-SECONDARY_DOT)") (class "Default")
      (node (ref "C127") (pin "1") (pinfunction "1_1") (pintype "passive"))
      (node (ref "T2") (pin "1") (pinfunction "SECONDARY_DOT_1") (pintype "passive"))
    )
    (net (code "38") (name "Net-(T3-PRIMARY_DOT)") (class "Default")
      (node (ref "C152") (pin "1") (pinfunction "1_1") (pintype "passive"))
      (node (ref "T3") (pin "5") (pinfunction "PRIMARY_DOT_5") (pintype "passive"))
    )
    (net (code "39") (name "Net-(T3-SECONARY_CT)") (class "Default")
      (node (ref "C153") (pin "2") (pinfunction "2_2") (pintype "passive"))
      (node (ref "R61") (pin "2") (pinfunction "2_2") (pintype "passive"))
      (node (ref "R63") (pin "1") (pinfunction "1_1") (pintype "passive"))
      (node (ref "R87") (pin "2") (pinfunction "2_2") (pintype "passive"))
      (node (ref "R88") (pin "1") (pinfunction "1_1") (pintype "passive"))
      (node (ref "T3") (pin "2") (pinfunction "SECONARY_CT_2") (pintype "passive"))
    )
    (net (code "40") (name "Net-(T3-SECONDARY)") (class "Default")
      (node (ref "R88") (pin "2") (pinfunction "2_2") (pintype "passive"))
      (node (ref "R89") (pin "1") (pinfunction "1_1") (pintype "passive"))
      (node (ref "T3") (pin "3") (pinfunction "SECONDARY_3") (pintype "passive"))
    )
    (net (code "41") (name "Net-(T3-SECONDARY_DOT)") (class "Default")
      (node (ref "R51") (pin "1") (pinfunction "1_1") (pintype "passive"))
      (node (ref "R87") (pin "1") (pinfunction "1_1") (pintype "passive"))
      (node (ref "T3") (pin "1") (pinfunction "SECONDARY_DOT_1") (pintype "passive"))
    )
    (net (code "42") (name "Net-(T4-CT)") (class "Default")
      (node (ref "C154") (pin "2") (pinfunction "2_2") (pintype "passive"))
      (node (ref "C156") (pin "1") (pinfunction "1_1") (pintype "passive"))
      (node (ref "C157") (pin "2") (pinfunction "2_2") (pintype "passive"))
      (node (ref "L49") (pin "2") (pinfunction "2_2") (pintype "passive"))
      (node (ref "T4") (pin "2") (pinfunction "CT_2") (pintype "passive"))
    )
    (net (code "43") (name "Net-(T4-PRIMARY)") (class "Default")
      (node (ref "C155") (pin "1") (pinfunction "1_1") (pintype "passive"))
      (node (ref "C210") (pin "1") (pinfunction "1_1") (pintype "passive"))
      (node (ref "T4") (pin "1") (pinfunction "PRIMARY_1") (pintype "passive"))
      (node (ref "VT4") (pin "3") (pinfunction "D_3") (pintype "passive"))
    )
    (net (code "44") (name "Net-(T4-PRIMARY_DOT)") (class "Default")
      (node (ref "C146") (pin "1") (pinfunction "1_1") (pintype "passive"))
      (node (ref "C98") (pin "1") (pinfunction "1_1") (pintype "passive"))
      (node (ref "T4") (pin "3") (pinfunction "PRIMARY_DOT_3") (pintype "passive"))
      (node (ref "VT3") (pin "3") (pinfunction "D_3") (pintype "passive"))
    )
    (net (code "45") (name "Net-(T4-SECONDARY_DOT)") (class "Default")
      (node (ref "T4") (pin "4") (pinfunction "SECONDARY_DOT_4") (pintype "passive"))
      (node (ref "XW4") (pin "1") (pinfunction "1_1") (pintype "passive"))
    )
    (net (code "46") (name "Net-(VT1-D)") (class "Default")
      (node (ref "C124") (pin "2") (pinfunction "2_2") (pintype "passive"))
      (node (ref "C127") (pin "2") (pinfunction "2_2") (pintype "passive"))
      (node (ref "L44") (pin "2") (pinfunction "2_2") (pintype "passive"))
      (node (ref "VT1") (pin "3") (pinfunction "D_3") (pintype "passive"))
    )
    (net (code "47") (name "Net-(VT1-GATE)") (class "Default")
      (node (ref "C126") (pin "1") (pinfunction "1_1") (pintype "passive"))
      (node (ref "R45") (pin "2") (pinfunction "2_2") (pintype "passive"))
      (node (ref "R46") (pin "2") (pinfunction "2_2") (pintype "passive"))
      (node (ref "VT1") (pin "1") (pinfunction "GATE_1") (pintype "passive"))
    )
    (net (code "48") (name "Net-(VT1-S)") (class "Default")
      (node (ref "C129") (pin "1") (pinfunction "1_1") (pintype "passive"))
      (node (ref "C130") (pin "1") (pinfunction "1_1") (pintype "passive"))
      (node (ref "R47") (pin "1") (pinfunction "1_1") (pintype "passive"))
      (node (ref "R85") (pin "2") (pinfunction "2_2") (pintype "passive"))
      (node (ref "VT1") (pin "2") (pinfunction "S_2") (pintype "passive"))
    )
    (net (code "49") (name "Net-(VT2-D)") (class "Default")
      (node (ref "C132") (pin "2") (pinfunction "2_2") (pintype "passive"))
      (node (ref "C143") (pin "2") (pinfunction "2_2") (pintype "passive"))
      (node (ref "L47") (pin "1") (pinfunction "1_1") (pintype "passive"))
      (node (ref "VT2") (pin "3") (pinfunction "D_3") (pintype "passive"))
    )
    (net (code "50") (name "Net-(VT2-GATE)") (class "Default")
      (node (ref "C139") (pin "1") (pinfunction "1_1") (pintype "passive"))
      (node (ref "R56") (pin "1") (pinfunction "1_1") (pintype "passive"))
      (node (ref "R57") (pin "1") (pinfunction "1_1") (pintype "passive"))
      (node (ref "VT2") (pin "1") (pinfunction "GATE_1") (pintype "passive"))
    )
    (net (code "51") (name "Net-(VT2-S)") (class "Default")
      (node (ref "C133") (pin "2") (pinfunction "2_2") (pintype "passive"))
      (node (ref "C134") (pin "2") (pinfunction "2_2") (pintype "passive"))
      (node (ref "R48") (pin "2") (pinfunction "2_2") (pintype "passive"))
      (node (ref "R86") (pin "2") (pinfunction "2_2") (pintype "passive"))
      (node (ref "VT2") (pin "2") (pinfunction "S_2") (pintype "passive"))
    )
    (net (code "52") (name "Net-(VT3-GATE)") (class "Default")
      (node (ref "R51") (pin "2") (pinfunction "2_2") (pintype "passive"))
      (node (ref "R64") (pin "1") (pinfunction "1_1") (pintype "passive"))
      (node (ref "VT3") (pin "1") (pinfunction "GATE_1") (pintype "passive"))
    )
    (net (code "53") (name "Net-(VT4-GATE)") (class "Default")
      (node (ref "R65") (pin "2") (pinfunction "2_2") (pintype "passive"))
      (node (ref "R89") (pin "2") (pinfunction "2_2") (pintype "passive"))
      (node (ref "VT4") (pin "1") (pinfunction "GATE_1") (pintype "passive"))
    )
    (net (code "54") (name "RELAY_TX") (class "Default")
      (node (ref "C125") (pin "1") (pinfunction "1_1") (pintype "passive"))
      (node (ref "K1") (pin "1") (pintype "passive"))
      (node (ref "VD1") (pin "3") (pinfunction "K_3") (pintype "passive"))
      (node (ref "VT6") (pin "3") (pinfunction "C_3") (pintype "passive"))
    )
    (net (code "55") (name "RF_3V3") (class "Default")
      (node (ref "L45") (pin "2") (pinfunction "2_2") (pintype "passive"))
    )
    (net (code "56") (name "TX_EN") (class "Default")
      (node (ref "C209") (pin "1") (pinfunction "1_1") (pintype "passive"))
      (node (ref "VT6") (pin "1") (pinfunction "B_1") (pintype "passive"))
    )
    (net (code "57") (name "VDD_12V") (class "Default")
      (node (ref "L42") (pin "1") (pinfunction "1_1") (pintype "passive"))
      (node (ref "L49") (pin "1") (pinfunction "1_1") (pintype "passive"))
    )
    (net (code "58") (name "VDD_12VRF") (class "Default")
      (node (ref "C208") (pin "1") (pinfunction "1_1") (pintype "passive"))
      (node (ref "C93") (pin "2") (pinfunction "2_2") (pintype "passive"))
      (node (ref "DA21") (pin "13") (pinfunction "EN_13") (pintype "passive"))
      (node (ref "DA21") (pin "15") (pinfunction "IN_15") (pintype "passive"))
      (node (ref "DA21") (pin "16") (pinfunction "IN_16") (pintype "passive"))
      (node (ref "K1") (pin "8") (pintype "passive"))
      (node (ref "L42") (pin "2") (pinfunction "2_2") (pintype "passive"))
    )
    (net (code "59") (name "VDD_RFIN") (class "Default")
      (node (ref "C122") (pin "2") (pinfunction "2_2") (pintype "passive"))
      (node (ref "C123") (pin "1") (pinfunction "1_1") (pintype "passive"))
      (node (ref "C149") (pin "2") (pinfunction "2_2") (pintype "passive"))
      (node (ref "C150") (pin "1") (pinfunction "1_1") (pintype "passive"))
      (node (ref "C94") (pin "2") (pinfunction "2_2") (pintype "passive"))
      (node (ref "C99") (pin "1") (pinfunction "1_1") (pintype "passive"))
      (node (ref "DA21") (pin "1") (pinfunction "OUT_1") (pintype "passive"))
      (node (ref "DA21") (pin "20") (pinfunction "OUT_20") (pintype "passive"))
      (node (ref "DA21") (pin "3") (pinfunction "SENSE_3") (pintype "passive"))
      (node (ref "L44") (pin "1") (pinfunction "1_1") (pintype "passive"))
      (node (ref "L46") (pin "1") (pinfunction "1_1") (pintype "passive"))
      (node (ref "L47") (pin "2") (pinfunction "2_2") (pintype "passive"))
      (node (ref "R44") (pin "2") (pinfunction "2_2") (pintype "passive"))
      (node (ref "R59") (pin "1") (pinfunction "1_1") (pintype "passive"))
    )
    (net (code "60") (name "unconnected-(DA21-0P1V-Pad12)") (class "Default")
      (node (ref "DA21") (pin "12") (pinfunction "0P1V_12") (pintype "passive"))
    )
    (net (code "61") (name "unconnected-(DA21-0P8V-Pad9)") (class "Default")
      (node (ref "DA21") (pin "9") (pinfunction "0P8V_9") (pintype "passive"))
    )
    (net (code "62") (name "unconnected-(DA21-1P6V-Pad8)") (class "Default")
      (node (ref "DA21") (pin "8") (pinfunction "1P6V_8") (pintype "passive"))
    )
    (net (code "63") (name "unconnected-(DA21-3P2V-Pad6)") (class "Default")
      (node (ref "DA21") (pin "6") (pinfunction "3P2V_6") (pintype "passive"))
    )
    (net (code "64") (name "unconnected-(DA21-6P4V2-Pad4)") (class "Default")
      (node (ref "DA21") (pin "4") (pinfunction "6P4V2_4") (pintype "passive"))
    )
    (net (code "65") (name "unconnected-(DA29-GND-Pad5)") (class "Default")
      (node (ref "DA29") (pin "5") (pinfunction "GND_5") (pintype "passive"))
    )
    (net (code "66") (name "unconnected-(K1-Pad2)") (class "Default")
      (node (ref "K1") (pin "2") (pintype "passive"))
    )
    (net (code "67") (name "unconnected-(K1-Pad3)") (class "Default")
      (node (ref "K1") (pin "3") (pintype "passive"))
    )
    (net (code "68") (name "unconnected-(K1-Pad4)") (class "Default")
      (node (ref "K1") (pin "4") (pintype "passive"))
    )
  )
)
